# POWER_SUPPLY_5VDC.net
KiCad netlist of a schematic drawn in EAGLE
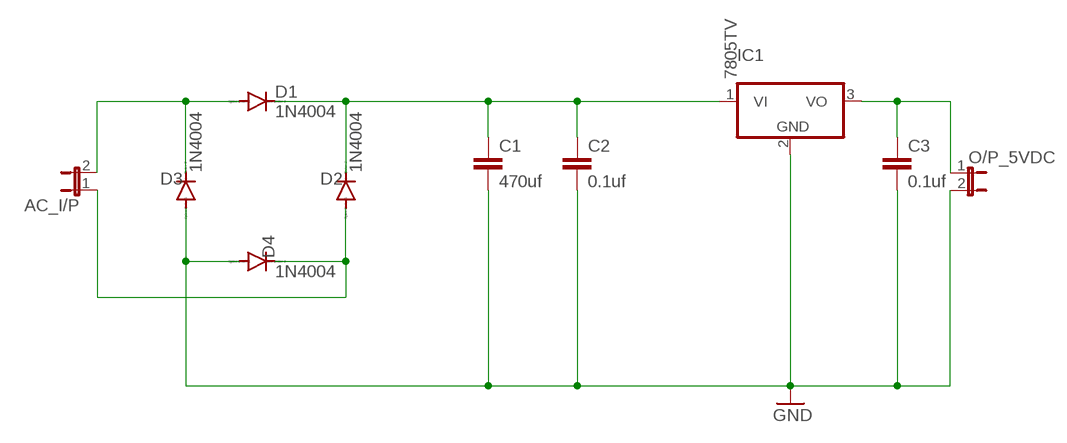
[diagram p0: schematic, sheet 1]

(export (version "E")
  (design (tool "Eeschema 10.0.6"))
  (components
    (comp (ref "AC_I/P")
      (value "12VAC")
      (footprint "eagle-import:JP1")
      (libsource (lib "eagle-import") (part "JP1E"))
    )
    (comp (ref "C1")
      (value "470uf")
      (footprint "eagle-import:C025-024X044")
      (libsource (lib "eagle-import") (part "C-EU025-024X044"))
    )
    (comp (ref "C2")
      (value "0.1uf")
      (footprint "eagle-import:C025-024X044")
      (libsource (lib "eagle-import") (part "C-EU025-024X044"))
    )
    (comp (ref "C3")
      (value "0.1uf")
      (footprint "eagle-import:C025-024X044")
      (libsource (lib "eagle-import") (part "C-EU025-024X044"))
    )
    (comp (ref "D1")
      (value "1N4004")
      (footprint "eagle-import:DO41-10")
      (libsource (lib "eagle-import") (part "1N4004"))
    )
    (comp (ref "D2")
      (value "1N4004")
      (footprint "eagle-import:DO41-10")
      (libsource (lib "eagle-import") (part "1N4004"))
    )
    (comp (ref "D3")
      (value "1N4004")
      (footprint "eagle-import:DO41-10")
      (libsource (lib "eagle-import") (part "1N4004"))
    )
    (comp (ref "D4")
      (value "1N4004")
      (footprint "eagle-import:DO41-10")
      (libsource (lib "eagle-import") (part "1N4004"))
    )
    (comp (ref "IC1")
      (value "7805TV")
      (footprint "eagle-import:TO220V")
      (libsource (lib "eagle-import") (part "78TV05"))
    )
    (comp (ref "O/P_5VDC")
      (value "5VDC")
      (footprint "eagle-import:JP1")
      (libsource (lib "eagle-import") (part "JP1E"))
    )
  )
  (nets
    (net (code "1") (name "GND") (class "Default")
      (node (ref "C1") (pin "2") (pinfunction "2_2") (pintype "passive"))
      (node (ref "C2") (pin "2") (pinfunction "2_2") (pintype "passive"))
      (node (ref "C3") (pin "2") (pinfunction "2_2") (pintype "passive"))
      (node (ref "D3") (pin "A") (pinfunction "A_A") (pintype "passive"))
      (node (ref "D4") (pin "A") (pinfunction "A_A") (pintype "passive"))
      (node (ref "IC1") (pin "2") (pinfunction "GND_2") (pintype "passive"))
      (node (ref "O/P_5VDC") (pin "2") (pinfunction "2_2") (pintype "passive"))
    )
    (net (code "2") (name "Net-(AC_I/P-Pad1)") (class "Default")
      (node (ref "AC_I/P") (pin "1") (pinfunction "1_1") (pintype "passive"))
      (node (ref "D2") (pin "A") (pinfunction "A_A") (pintype "passive"))
      (node (ref "D4") (pin "C") (pinfunction "C_C") (pintype "passive"))
    )
    (net (code "3") (name "Net-(AC_I/P-Pad2)") (class "Default")
      (node (ref "AC_I/P") (pin "2") (pinfunction "2_2") (pintype "passive"))
      (node (ref "D1") (pin "A") (pinfunction "A_A") (pintype "passive"))
      (node (ref "D3") (pin "C") (pinfunction "C_C") (pintype "passive"))
    )
    (net (code "4") (name "Net-(IC1-VI)") (class "Default")
      (node (ref "C1") (pin "1") (pinfunction "1_1") (pintype "passive"))
      (node (ref "C2") (pin "1") (pinfunction "1_1") (pintype "passive"))
      (node (ref "D1") (pin "C") (pinfunction "C_C") (pintype "passive"))
      (node (ref "D2") (pin "C") (pinfunction "C_C") (pintype "passive"))
      (node (ref "IC1") (pin "1") (pinfunction "VI_1") (pintype "input"))
    )
    (net (code "5") (name "Net-(IC1-VO)") (class "Default")
      (node (ref "C3") (pin "1") (pinfunction "1_1") (pintype "passive"))
      (node (ref "IC1") (pin "3") (pinfunction "VO_3") (pintype "passive"))
      (node (ref "O/P_5VDC") (pin "1") (pinfunction "1_1") (pintype "passive"))
    )
  )
)
